# TCAN1146_PINOUT.net
KiCad netlist of a schematic drawn in Altium Designer
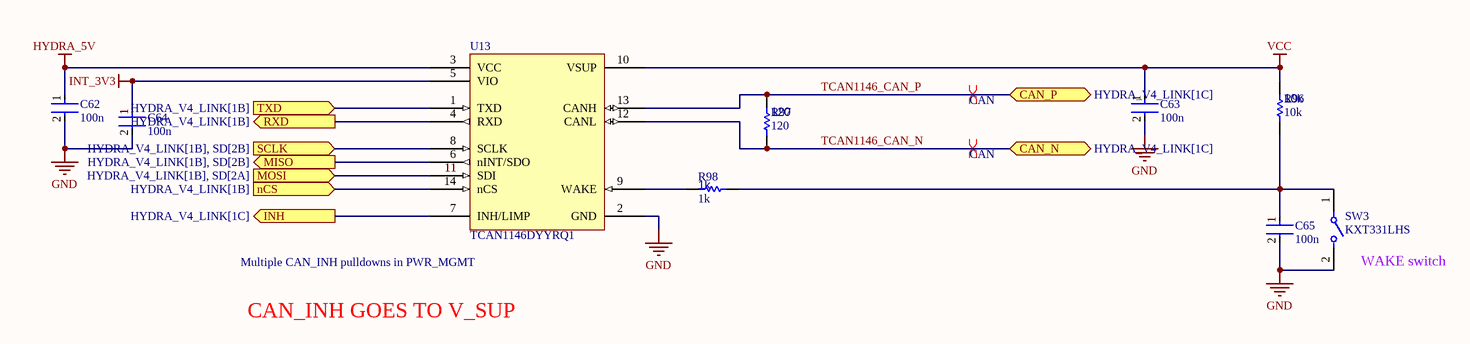
[diagram p0: TCAN1146_PINOUT.SchDoc]

(export (version "E")
  (design (tool "Eeschema 10.0.6"))
  (components
    (comp (ref "C62")
      (value "100n")
      (footprint "FP-0402-L_1_0_0_05-W_0_5-IPC_A")
      (description "LARGE PADS, 0402 CAP, CHANGE COMMENT TO MATCH REAL P/N")
      (libsource (lib "Space Concordia") (part "b4654b650e69147ec39a6b967a45e02"))
    )
    (comp (ref "C63")
      (value "100n")
      (footprint "FP-0402-L_1_0_0_05-W_0_5-IPC_A")
      (description "LARGE PADS, 0402 CAP, CHANGE COMMENT TO MATCH REAL P/N")
      (libsource (lib "Space Concordia") (part "b4654b650e69147ec39a6b967a45e02"))
    )
    (comp (ref "C64")
      (value "100n")
      (footprint "FP-0402-L_1_0_0_05-W_0_5-IPC_A")
      (description "LARGE PADS, 0402 CAP, CHANGE COMMENT TO MATCH REAL P/N")
      (libsource (lib "Space Concordia") (part "b4654b650e69147ec39a6b967a45e02"))
    )
    (comp (ref "C65")
      (value "100n")
      (footprint "FP-0402-L_1_0_0_05-W_0_5-IPC_A")
      (description "LARGE PADS, 0402 CAP, CHANGE COMMENT TO MATCH REAL P/N")
      (libsource (lib "Space Concordia") (part "b4654b650e69147ec39a6b967a45e02"))
    )
    (comp (ref "R96")
      (value "10k")
      (footprint "R0603B")
      (description "Resistor")
      (fields (field (name "ALTIUM_VALUE") "10k"))
      (libsource (lib "Space Concordia") (part "Resistor"))
    )
    (comp (ref "R97")
      (value "120")
      (footprint "R0603B")
      (description "Resistor")
      (fields (field (name "ALTIUM_VALUE") "120"))
      (libsource (lib "Space Concordia") (part "Resistor"))
    )
    (comp (ref "R98")
      (value "1k")
      (footprint "R0603B")
      (description "Resistor")
      (fields (field (name "ALTIUM_VALUE") "1k"))
      (libsource (lib "Space Concordia") (part "Resistor"))
    )
    (comp (ref "SW3")
      (value "KXT331LHS")
      (footprint "FP-KXT331LHS-MFG")
      (description "SWITCH TACTILE SPST-NO 0.02A 15V")
      (libsource (lib "Altium Content Vault") (part "bb27bde45df87f1f469753f287ef5ae"))
    )
    (comp (ref "U13")
      (value "TCAN1146DYYRQ1")
      (footprint "TCAN1146DYYRQ1-Footprint-1")
      (libsource (lib "Space Concordia") (part "CMP-015-00012-2"))
    )
  )
  (nets
    (net (code "1") (name "/INH") (class "Default")
      (node (ref "U13") (pin "7") (pinfunction "INH/LIMP_7") (pintype "passive"))
    )
    (net (code "2") (name "/MISO") (class "Default")
      (node (ref "U13") (pin "6") (pinfunction "nINT/SDO_6") (pintype "output"))
    )
    (net (code "3") (name "/MOSI") (class "Default")
      (node (ref "U13") (pin "11") (pinfunction "SDI_11") (pintype "input"))
    )
    (net (code "4") (name "/RXD") (class "Default")
      (node (ref "U13") (pin "4") (pinfunction "RXD_4") (pintype "output"))
    )
    (net (code "5") (name "/SCLK") (class "Default")
      (node (ref "U13") (pin "8") (pinfunction "SCLK_8") (pintype "input"))
    )
    (net (code "6") (name "/TCAN1146_CAN_N") (class "Default")
      (node (ref "R97") (pin "1") (pinfunction "1_1") (pintype "passive"))
      (node (ref "U13") (pin "12") (pinfunction "CANL_12") (pintype "bidirectional"))
    )
    (net (code "7") (name "/TCAN1146_CAN_P") (class "Default")
      (node (ref "R97") (pin "2") (pinfunction "2_2") (pintype "passive"))
      (node (ref "U13") (pin "13") (pinfunction "CANH_13") (pintype "bidirectional"))
    )
    (net (code "8") (name "/TXD") (class "Default")
      (node (ref "U13") (pin "1") (pinfunction "TXD_1") (pintype "input"))
    )
    (net (code "9") (name "/nCS") (class "Default")
      (node (ref "U13") (pin "14") (pinfunction "nCS_14") (pintype "input"))
    )
    (net (code "10") (name "GND") (class "Default")
      (node (ref "C62") (pin "2") (pinfunction "2_2") (pintype "passive"))
      (node (ref "C63") (pin "2") (pinfunction "2_2") (pintype "passive"))
      (node (ref "C64") (pin "2") (pinfunction "2_2") (pintype "passive"))
      (node (ref "C65") (pin "2") (pinfunction "2_2") (pintype "passive"))
      (node (ref "SW3") (pin "2") (pinfunction "2_2") (pintype "passive"))
      (node (ref "U13") (pin "2") (pinfunction "GND_2") (pintype "power_in"))
    )
    (net (code "11") (name "HYDRA_5V") (class "Default")
      (node (ref "C62") (pin "1") (pinfunction "1_1") (pintype "passive"))
      (node (ref "U13") (pin "3") (pinfunction "VCC_3") (pintype "power_in"))
    )
    (net (code "12") (name "INT_3V3") (class "Default")
      (node (ref "C64") (pin "1") (pinfunction "1_1") (pintype "passive"))
      (node (ref "U13") (pin "5") (pinfunction "VIO_5") (pintype "power_in"))
    )
    (net (code "13") (name "Net-(C65-Pad1)") (class "Default")
      (node (ref "C65") (pin "1") (pinfunction "1_1") (pintype "passive"))
      (node (ref "R96") (pin "1") (pinfunction "1_1") (pintype "passive"))
      (node (ref "R98") (pin "1") (pinfunction "1_1") (pintype "passive"))
      (node (ref "SW3") (pin "1") (pinfunction "1_1") (pintype "passive"))
    )
    (net (code "14") (name "Net-(U13-WAKE)") (class "Default")
      (node (ref "R98") (pin "2") (pinfunction "2_2") (pintype "passive"))
      (node (ref "U13") (pin "9") (pinfunction "WAKE_9") (pintype "input"))
    )
    (net (code "15") (name "VCC") (class "Default")
      (node (ref "C63") (pin "1") (pinfunction "1_1") (pintype "passive"))
      (node (ref "R96") (pin "2") (pinfunction "2_2") (pintype "passive"))
      (node (ref "U13") (pin "10") (pinfunction "VSUP_10") (pintype "power_in"))
    )
  )
)
